# Sheet3.net
KiCad netlist of a schematic drawn in Altium Designer
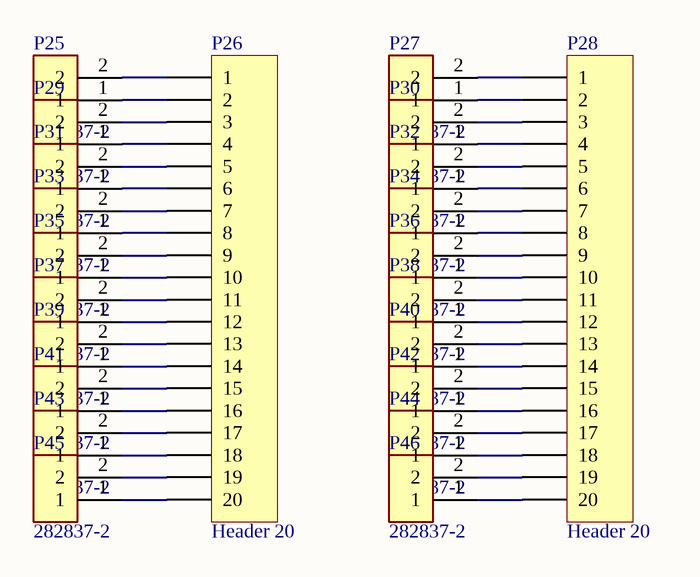
[diagram p0: Sheet3.SchDoc]

(export (version "E")
  (design (tool "Eeschema 10.0.6"))
  (components
    (comp (ref "P25")
      (value "282837-2")
      (footprint "TE_282837-2")
      (fields (field (name "MF") "TE Connectivity"))
      (libsource (lib "282837-2") (part "282837-2"))
    )
    (comp (ref "P26")
      (value "Header 20")
      (footprint "HDR1X20")
      (description "Header, 20-Pin")
      (fields (field (name "PUBLISHER") "Altium Limited"))
      (libsource (lib "Miscellaneous Connectors") (part "Header 20"))
    )
    (comp (ref "P27")
      (value "282837-2")
      (footprint "TE_282837-2")
      (fields (field (name "MF") "TE Connectivity"))
      (libsource (lib "282837-2") (part "282837-2"))
    )
    (comp (ref "P28")
      (value "Header 20")
      (footprint "HDR1X20")
      (description "Header, 20-Pin")
      (fields (field (name "PUBLISHER") "Altium Limited"))
      (libsource (lib "Miscellaneous Connectors") (part "Header 20"))
    )
    (comp (ref "P29")
      (value "282837-2")
      (footprint "TE_282837-2")
      (fields (field (name "MF") "TE Connectivity"))
      (libsource (lib "282837-2") (part "282837-2"))
    )
    (comp (ref "P30")
      (value "282837-2")
      (footprint "TE_282837-2")
      (fields (field (name "MF") "TE Connectivity"))
      (libsource (lib "282837-2") (part "282837-2"))
    )
    (comp (ref "P31")
      (value "282837-2")
      (footprint "TE_282837-2")
      (fields (field (name "MF") "TE Connectivity"))
      (libsource (lib "282837-2") (part "282837-2"))
    )
    (comp (ref "P32")
      (value "282837-2")
      (footprint "TE_282837-2")
      (fields (field (name "MF") "TE Connectivity"))
      (libsource (lib "282837-2") (part "282837-2"))
    )
    (comp (ref "P33")
      (value "282837-2")
      (footprint "TE_282837-2")
      (fields (field (name "MF") "TE Connectivity"))
      (libsource (lib "282837-2") (part "282837-2"))
    )
    (comp (ref "P34")
      (value "282837-2")
      (footprint "TE_282837-2")
      (fields (field (name "MF") "TE Connectivity"))
      (libsource (lib "282837-2") (part "282837-2"))
    )
    (comp (ref "P35")
      (value "282837-2")
      (footprint "TE_282837-2")
      (fields (field (name "MF") "TE Connectivity"))
      (libsource (lib "282837-2") (part "282837-2"))
    )
    (comp (ref "P36")
      (value "282837-2")
      (footprint "TE_282837-2")
      (fields (field (name "MF") "TE Connectivity"))
      (libsource (lib "282837-2") (part "282837-2"))
    )
    (comp (ref "P37")
      (value "282837-2")
      (footprint "TE_282837-2")
      (fields (field (name "MF") "TE Connectivity"))
      (libsource (lib "282837-2") (part "282837-2"))
    )
    (comp (ref "P38")
      (value "282837-2")
      (footprint "TE_282837-2")
      (fields (field (name "MF") "TE Connectivity"))
      (libsource (lib "282837-2") (part "282837-2"))
    )
    (comp (ref "P39")
      (value "282837-2")
      (footprint "TE_282837-2")
      (fields (field (name "MF") "TE Connectivity"))
      (libsource (lib "282837-2") (part "282837-2"))
    )
    (comp (ref "P40")
      (value "282837-2")
      (footprint "TE_282837-2")
      (fields (field (name "MF") "TE Connectivity"))
      (libsource (lib "282837-2") (part "282837-2"))
    )
    (comp (ref "P41")
      (value "282837-2")
      (footprint "TE_282837-2")
      (fields (field (name "MF") "TE Connectivity"))
      (libsource (lib "282837-2") (part "282837-2"))
    )
    (comp (ref "P42")
      (value "282837-2")
      (footprint "TE_282837-2")
      (fields (field (name "MF") "TE Connectivity"))
      (libsource (lib "282837-2") (part "282837-2"))
    )
    (comp (ref "P43")
      (value "282837-2")
      (footprint "TE_282837-2")
      (fields (field (name "MF") "TE Connectivity"))
      (libsource (lib "282837-2") (part "282837-2"))
    )
    (comp (ref "P44")
      (value "282837-2")
      (footprint "TE_282837-2")
      (fields (field (name "MF") "TE Connectivity"))
      (libsource (lib "282837-2") (part "282837-2"))
    )
    (comp (ref "P45")
      (value "282837-2")
      (footprint "TE_282837-2")
      (fields (field (name "MF") "TE Connectivity"))
      (libsource (lib "282837-2") (part "282837-2"))
    )
    (comp (ref "P46")
      (value "282837-2")
      (footprint "TE_282837-2")
      (fields (field (name "MF") "TE Connectivity"))
      (libsource (lib "282837-2") (part "282837-2"))
    )
  )
  (nets
    (net (code "1") (name "Net-(P25-Pad1)") (class "Default")
      (node (ref "P25") (pin "1") (pinfunction "1_1") (pintype "passive"))
      (node (ref "P26") (pin "2") (pinfunction "2_2") (pintype "passive"))
    )
    (net (code "2") (name "Net-(P25-Pad2)") (class "Default")
      (node (ref "P25") (pin "2") (pinfunction "2_2") (pintype "passive"))
      (node (ref "P26") (pin "1") (pinfunction "1_1") (pintype "passive"))
    )
    (net (code "3") (name "Net-(P26-Pad3)") (class "Default")
      (node (ref "P26") (pin "3") (pinfunction "3_3") (pintype "passive"))
      (node (ref "P29") (pin "2") (pinfunction "2_2") (pintype "passive"))
    )
    (net (code "4") (name "Net-(P26-Pad4)") (class "Default")
      (node (ref "P26") (pin "4") (pinfunction "4_4") (pintype "passive"))
      (node (ref "P29") (pin "1") (pinfunction "1_1") (pintype "passive"))
    )
    (net (code "5") (name "Net-(P26-Pad5)") (class "Default")
      (node (ref "P26") (pin "5") (pinfunction "5_5") (pintype "passive"))
      (node (ref "P31") (pin "2") (pinfunction "2_2") (pintype "passive"))
    )
    (net (code "6") (name "Net-(P26-Pad6)") (class "Default")
      (node (ref "P26") (pin "6") (pinfunction "6_6") (pintype "passive"))
      (node (ref "P31") (pin "1") (pinfunction "1_1") (pintype "passive"))
    )
    (net (code "7") (name "Net-(P26-Pad7)") (class "Default")
      (node (ref "P26") (pin "7") (pinfunction "7_7") (pintype "passive"))
      (node (ref "P33") (pin "2") (pinfunction "2_2") (pintype "passive"))
    )
    (net (code "8") (name "Net-(P26-Pad8)") (class "Default")
      (node (ref "P26") (pin "8") (pinfunction "8_8") (pintype "passive"))
      (node (ref "P33") (pin "1") (pinfunction "1_1") (pintype "passive"))
    )
    (net (code "9") (name "Net-(P26-Pad9)") (class "Default")
      (node (ref "P26") (pin "9") (pinfunction "9_9") (pintype "passive"))
      (node (ref "P35") (pin "2") (pinfunction "2_2") (pintype "passive"))
    )
    (net (code "10") (name "Net-(P26-Pad10)") (class "Default")
      (node (ref "P26") (pin "10") (pinfunction "10_10") (pintype "passive"))
      (node (ref "P35") (pin "1") (pinfunction "1_1") (pintype "passive"))
    )
    (net (code "11") (name "Net-(P26-Pad11)") (class "Default")
      (node (ref "P26") (pin "11") (pinfunction "11_11") (pintype "passive"))
      (node (ref "P37") (pin "2") (pinfunction "2_2") (pintype "passive"))
    )
    (net (code "12") (name "Net-(P26-Pad12)") (class "Default")
      (node (ref "P26") (pin "12") (pinfunction "12_12") (pintype "passive"))
      (node (ref "P37") (pin "1") (pinfunction "1_1") (pintype "passive"))
    )
    (net (code "13") (name "Net-(P26-Pad13)") (class "Default")
      (node (ref "P26") (pin "13") (pinfunction "13_13") (pintype "passive"))
      (node (ref "P39") (pin "2") (pinfunction "2_2") (pintype "passive"))
    )
    (net (code "14") (name "Net-(P26-Pad14)") (class "Default")
      (node (ref "P26") (pin "14") (pinfunction "14_14") (pintype "passive"))
      (node (ref "P39") (pin "1") (pinfunction "1_1") (pintype "passive"))
    )
    (net (code "15") (name "Net-(P26-Pad15)") (class "Default")
      (node (ref "P26") (pin "15") (pinfunction "15_15") (pintype "passive"))
      (node (ref "P41") (pin "2") (pinfunction "2_2") (pintype "passive"))
    )
    (net (code "16") (name "Net-(P26-Pad16)") (class "Default")
      (node (ref "P26") (pin "16") (pinfunction "16_16") (pintype "passive"))
      (node (ref "P41") (pin "1") (pinfunction "1_1") (pintype "passive"))
    )
    (net (code "17") (name "Net-(P26-Pad17)") (class "Default")
      (node (ref "P26") (pin "17") (pinfunction "17_17") (pintype "passive"))
      (node (ref "P43") (pin "2") (pinfunction "2_2") (pintype "passive"))
    )
    (net (code "18") (name "Net-(P26-Pad18)") (class "Default")
      (node (ref "P26") (pin "18") (pinfunction "18_18") (pintype "passive"))
      (node (ref "P43") (pin "1") (pinfunction "1_1") (pintype "passive"))
    )
    (net (code "19") (name "Net-(P26-Pad19)") (class "Default")
      (node (ref "P26") (pin "19") (pinfunction "19_19") (pintype "passive"))
      (node (ref "P45") (pin "2") (pinfunction "2_2") (pintype "passive"))
    )
    (net (code "20") (name "Net-(P26-Pad20)") (class "Default")
      (node (ref "P26") (pin "20") (pinfunction "20_20") (pintype "passive"))
      (node (ref "P45") (pin "1") (pinfunction "1_1") (pintype "passive"))
    )
    (net (code "21") (name "Net-(P27-Pad1)") (class "Default")
      (node (ref "P27") (pin "1") (pinfunction "1_1") (pintype "passive"))
      (node (ref "P28") (pin "2") (pinfunction "2_2") (pintype "passive"))
    )
    (net (code "22") (name "Net-(P27-Pad2)") (class "Default")
      (node (ref "P27") (pin "2") (pinfunction "2_2") (pintype "passive"))
      (node (ref "P28") (pin "1") (pinfunction "1_1") (pintype "passive"))
    )
    (net (code "23") (name "Net-(P28-Pad3)") (class "Default")
      (node (ref "P28") (pin "3") (pinfunction "3_3") (pintype "passive"))
      (node (ref "P30") (pin "2") (pinfunction "2_2") (pintype "passive"))
    )
    (net (code "24") (name "Net-(P28-Pad4)") (class "Default")
      (node (ref "P28") (pin "4") (pinfunction "4_4") (pintype "passive"))
      (node (ref "P30") (pin "1") (pinfunction "1_1") (pintype "passive"))
    )
    (net (code "25") (name "Net-(P28-Pad5)") (class "Default")
      (node (ref "P28") (pin "5") (pinfunction "5_5") (pintype "passive"))
      (node (ref "P32") (pin "2") (pinfunction "2_2") (pintype "passive"))
    )
    (net (code "26") (name "Net-(P28-Pad6)") (class "Default")
      (node (ref "P28") (pin "6") (pinfunction "6_6") (pintype "passive"))
      (node (ref "P32") (pin "1") (pinfunction "1_1") (pintype "passive"))
    )
    (net (code "27") (name "Net-(P28-Pad7)") (class "Default")
      (node (ref "P28") (pin "7") (pinfunction "7_7") (pintype "passive"))
      (node (ref "P34") (pin "2") (pinfunction "2_2") (pintype "passive"))
    )
    (net (code "28") (name "Net-(P28-Pad8)") (class "Default")
      (node (ref "P28") (pin "8") (pinfunction "8_8") (pintype "passive"))
      (node (ref "P34") (pin "1") (pinfunction "1_1") (pintype "passive"))
    )
    (net (code "29") (name "Net-(P28-Pad9)") (class "Default")
      (node (ref "P28") (pin "9") (pinfunction "9_9") (pintype "passive"))
      (node (ref "P36") (pin "2") (pinfunction "2_2") (pintype "passive"))
    )
    (net (code "30") (name "Net-(P28-Pad10)") (class "Default")
      (node (ref "P28") (pin "10") (pinfunction "10_10") (pintype "passive"))
      (node (ref "P36") (pin "1") (pinfunction "1_1") (pintype "passive"))
    )
    (net (code "31") (name "Net-(P28-Pad11)") (class "Default")
      (node (ref "P28") (pin "11") (pinfunction "11_11") (pintype "passive"))
      (node (ref "P38") (pin "2") (pinfunction "2_2") (pintype "passive"))
    )
    (net (code "32") (name "Net-(P28-Pad12)") (class "Default")
      (node (ref "P28") (pin "12") (pinfunction "12_12") (pintype "passive"))
      (node (ref "P38") (pin "1") (pinfunction "1_1") (pintype "passive"))
    )
    (net (code "33") (name "Net-(P28-Pad13)") (class "Default")
      (node (ref "P28") (pin "13") (pinfunction "13_13") (pintype "passive"))
      (node (ref "P40") (pin "2") (pinfunction "2_2") (pintype "passive"))
    )
    (net (code "34") (name "Net-(P28-Pad14)") (class "Default")
      (node (ref "P28") (pin "14") (pinfunction "14_14") (pintype "passive"))
      (node (ref "P40") (pin "1") (pinfunction "1_1") (pintype "passive"))
    )
    (net (code "35") (name "Net-(P28-Pad15)") (class "Default")
      (node (ref "P28") (pin "15") (pinfunction "15_15") (pintype "passive"))
      (node (ref "P42") (pin "2") (pinfunction "2_2") (pintype "passive"))
    )
    (net (code "36") (name "Net-(P28-Pad16)") (class "Default")
      (node (ref "P28") (pin "16") (pinfunction "16_16") (pintype "passive"))
      (node (ref "P42") (pin "1") (pinfunction "1_1") (pintype "passive"))
    )
    (net (code "37") (name "Net-(P28-Pad17)") (class "Default")
      (node (ref "P28") (pin "17") (pinfunction "17_17") (pintype "passive"))
      (node (ref "P44") (pin "2") (pinfunction "2_2") (pintype "passive"))
    )
    (net (code "38") (name "Net-(P28-Pad18)") (class "Default")
      (node (ref "P28") (pin "18") (pinfunction "18_18") (pintype "passive"))
      (node (ref "P44") (pin "1") (pinfunction "1_1") (pintype "passive"))
    )
    (net (code "39") (name "Net-(P28-Pad19)") (class "Default")
      (node (ref "P28") (pin "19") (pinfunction "19_19") (pintype "passive"))
      (node (ref "P46") (pin "2") (pinfunction "2_2") (pintype "passive"))
    )
    (net (code "40") (name "Net-(P28-Pad20)") (class "Default")
      (node (ref "P28") (pin "20") (pinfunction "20_20") (pintype "passive"))
      (node (ref "P46") (pin "1") (pinfunction "1_1") (pintype "passive"))
    )
  )
)
